# prject_arkom_robot_running_folower.net
KiCad netlist of a schematic drawn in EAGLE
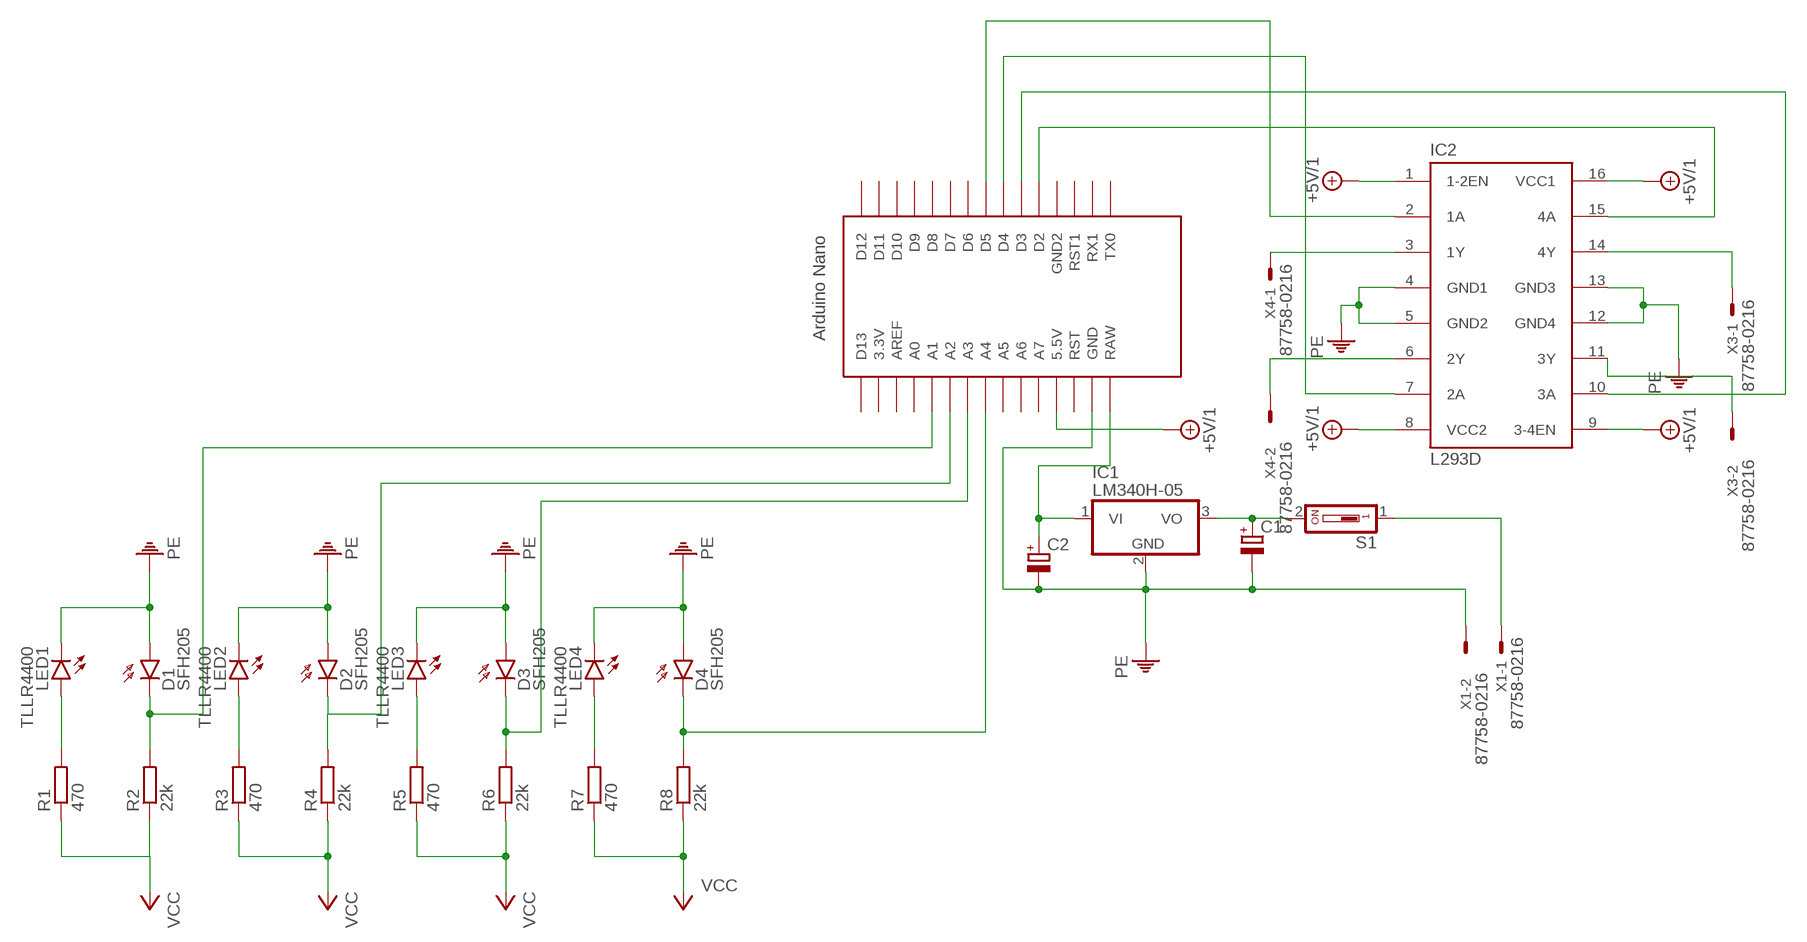
[diagram p0: schematic, sheet 1]

(export (version "E")
  (design (tool "Eeschema 10.0.6"))
  (components
    (comp (ref "C1")
      (value "CPOL-EUE2.5-7")
      (footprint "eagle-import:E2,5-7")
      (libsource (lib "eagle-import") (part "CPOL-EUE2.5-7"))
    )
    (comp (ref "C2")
      (value "CPOL-EUE2.5-7")
      (footprint "eagle-import:E2,5-7")
      (libsource (lib "eagle-import") (part "CPOL-EUE2.5-7"))
    )
    (comp (ref "D1")
      (value "SFH205")
      (footprint "eagle-import:SFH205")
      (libsource (lib "eagle-import") (part "SFH205"))
    )
    (comp (ref "D2")
      (value "SFH205")
      (footprint "eagle-import:SFH205")
      (libsource (lib "eagle-import") (part "SFH205"))
    )
    (comp (ref "D3")
      (value "SFH205")
      (footprint "eagle-import:SFH205")
      (libsource (lib "eagle-import") (part "SFH205"))
    )
    (comp (ref "D4")
      (value "SFH205")
      (footprint "eagle-import:SFH205")
      (libsource (lib "eagle-import") (part "SFH205"))
    )
    (comp (ref "IC1")
      (value "LM340H-05")
      (footprint "eagle-import:TO220H")
      (libsource (lib "eagle-import") (part "LM340?-H05"))
    )
    (comp (ref "IC2")
      (value "L293D")
      (footprint "eagle-import:DIL16")
      (libsource (lib "eagle-import") (part "L293D"))
    )
    (comp (ref "LED1")
      (value "TLLR4400")
      (footprint "eagle-import:LED3MM")
      (fields (field (name "MF") "VISHAY SEMICONDUCTOR"))
      (libsource (lib "eagle-import") (part "TLLR4400"))
    )
    (comp (ref "LED2")
      (value "TLLR4400")
      (footprint "eagle-import:LED3MM")
      (fields (field (name "MF") "VISHAY SEMICONDUCTOR"))
      (libsource (lib "eagle-import") (part "TLLR4400"))
    )
    (comp (ref "LED3")
      (value "TLLR4400")
      (footprint "eagle-import:LED3MM")
      (fields (field (name "MF") "VISHAY SEMICONDUCTOR"))
      (libsource (lib "eagle-import") (part "TLLR4400"))
    )
    (comp (ref "LED4")
      (value "TLLR4400")
      (footprint "eagle-import:LED3MM")
      (fields (field (name "MF") "VISHAY SEMICONDUCTOR"))
      (libsource (lib "eagle-import") (part "TLLR4400"))
    )
    (comp (ref "R1")
      (value "470")
      (footprint "eagle-import:0204_7")
      (libsource (lib "eagle-import") (part "R-EU_0204/7"))
    )
    (comp (ref "R2")
      (value "22k")
      (footprint "eagle-import:0204_7")
      (libsource (lib "eagle-import") (part "R-EU_0204/7"))
    )
    (comp (ref "R3")
      (value "470")
      (footprint "eagle-import:0204_7")
      (libsource (lib "eagle-import") (part "R-EU_0204/7"))
    )
    (comp (ref "R4")
      (value "22k")
      (footprint "eagle-import:0204_7")
      (libsource (lib "eagle-import") (part "R-EU_0204/7"))
    )
    (comp (ref "R5")
      (value "470")
      (footprint "eagle-import:0204_7")
      (libsource (lib "eagle-import") (part "R-EU_0204/7"))
    )
    (comp (ref "R6")
      (value "22k")
      (footprint "eagle-import:0204_7")
      (libsource (lib "eagle-import") (part "R-EU_0204/7"))
    )
    (comp (ref "R7")
      (value "470")
      (footprint "eagle-import:0204_7")
      (libsource (lib "eagle-import") (part "R-EU_0204/7"))
    )
    (comp (ref "R8")
      (value "22k")
      (footprint "eagle-import:0204_7")
      (libsource (lib "eagle-import") (part "R-EU_0204/7"))
    )
    (comp (ref "S1")
      (value "SD4-01")
      (footprint "eagle-import:SD4-01")
      (libsource (lib "eagle-import") (part "SD4-01"))
    )
    (comp (ref "U$1")
      (value "NANO")
      (footprint "eagle-import:NANO")
      (libsource (lib "eagle-import") (part "NANO"))
    )
    (comp (ref "X1")
      (value "87758-0216")
      (footprint "eagle-import:87758-0216")
      (fields (field (name "MF") "MOLEX"))
      (libsource (lib "eagle-import") (part "87758-0216"))
    )
    (comp (ref "X3")
      (value "87758-0216")
      (footprint "eagle-import:87758-0216")
      (fields (field (name "MF") "MOLEX"))
      (libsource (lib "eagle-import") (part "87758-0216"))
    )
    (comp (ref "X4")
      (value "87758-0216")
      (footprint "eagle-import:87758-0216")
      (fields (field (name "MF") "MOLEX"))
      (libsource (lib "eagle-import") (part "87758-0216"))
    )
  )
  (nets
    (net (code "1") (name "+5V{slash}1") (class "Default")
      (node (ref "IC2") (pin "1") (pinfunction "1-2EN_1") (pintype "input"))
      (node (ref "IC2") (pin "16") (pinfunction "VCC1_16") (pintype "power_in"))
      (node (ref "IC2") (pin "8") (pinfunction "VCC2_8") (pintype "power_in"))
      (node (ref "IC2") (pin "9") (pinfunction "3-4EN_9") (pintype "input"))
      (node (ref "U$1") (pin "5V") (pinfunction "5.5V_5V") (pintype "bidirectional"))
    )
    (net (code "2") (name "Net-(D1-C)") (class "Default")
      (node (ref "D1") (pin "K") (pinfunction "C_K") (pintype "passive"))
      (node (ref "R2") (pin "2") (pinfunction "2_2") (pintype "passive"))
      (node (ref "U$1") (pin "A1") (pinfunction "A1_A1") (pintype "bidirectional"))
    )
    (net (code "3") (name "Net-(D2-C)") (class "Default")
      (node (ref "D2") (pin "K") (pinfunction "C_K") (pintype "passive"))
      (node (ref "R4") (pin "2") (pinfunction "2_2") (pintype "passive"))
      (node (ref "U$1") (pin "A2") (pinfunction "A2_A2") (pintype "bidirectional"))
    )
    (net (code "4") (name "Net-(D3-C)") (class "Default")
      (node (ref "D3") (pin "K") (pinfunction "C_K") (pintype "passive"))
      (node (ref "R6") (pin "2") (pinfunction "2_2") (pintype "passive"))
      (node (ref "U$1") (pin "A3") (pinfunction "A3_A3") (pintype "bidirectional"))
    )
    (net (code "5") (name "Net-(D4-C)") (class "Default")
      (node (ref "D4") (pin "K") (pinfunction "C_K") (pintype "passive"))
      (node (ref "R8") (pin "2") (pinfunction "2_2") (pintype "passive"))
      (node (ref "U$1") (pin "A4") (pinfunction "A4_A4") (pintype "bidirectional"))
    )
    (net (code "6") (name "Net-(IC1-VI)") (class "Default")
      (node (ref "C2") (pin "+") (pinfunction "+_+") (pintype "passive"))
      (node (ref "IC1") (pin "1") (pinfunction "VI_1") (pintype "input"))
      (node (ref "U$1") (pin "RAW") (pinfunction "RAW_RAW") (pintype "bidirectional"))
    )
    (net (code "7") (name "Net-(IC1-VO)") (class "Default")
      (node (ref "C1") (pin "+") (pinfunction "+_+") (pintype "passive"))
      (node (ref "IC1") (pin "3") (pinfunction "VO_3") (pintype "passive"))
      (node (ref "S1") (pin "2") (pinfunction "2_2") (pintype "passive"))
    )
    (net (code "8") (name "Net-(IC2-1A)") (class "Default")
      (node (ref "IC2") (pin "2") (pinfunction "1A_2") (pintype "input"))
      (node (ref "U$1") (pin "D5") (pinfunction "D5_D5") (pintype "bidirectional"))
    )
    (net (code "9") (name "Net-(IC2-1Y)") (class "Default")
      (node (ref "IC2") (pin "3") (pinfunction "1Y_3") (pintype "output"))
      (node (ref "X4") (pin "1") (pinfunction "S_1") (pintype "passive"))
    )
    (net (code "10") (name "Net-(IC2-2A)") (class "Default")
      (node (ref "IC2") (pin "7") (pinfunction "2A_7") (pintype "input"))
      (node (ref "U$1") (pin "D4") (pinfunction "D4_D4") (pintype "bidirectional"))
    )
    (net (code "11") (name "Net-(IC2-2Y)") (class "Default")
      (node (ref "IC2") (pin "6") (pinfunction "2Y_6") (pintype "output"))
      (node (ref "X4") (pin "2") (pinfunction "S_2") (pintype "passive"))
    )
    (net (code "12") (name "Net-(IC2-3A)") (class "Default")
      (node (ref "IC2") (pin "10") (pinfunction "3A_10") (pintype "input"))
      (node (ref "U$1") (pin "D3") (pinfunction "D3_D3") (pintype "bidirectional"))
    )
    (net (code "13") (name "Net-(IC2-3Y)") (class "Default")
      (node (ref "IC2") (pin "11") (pinfunction "3Y_11") (pintype "output"))
      (node (ref "X3") (pin "2") (pinfunction "S_2") (pintype "passive"))
    )
    (net (code "14") (name "Net-(IC2-4A)") (class "Default")
      (node (ref "IC2") (pin "15") (pinfunction "4A_15") (pintype "input"))
      (node (ref "U$1") (pin "D2") (pinfunction "D2_D2") (pintype "bidirectional"))
    )
    (net (code "15") (name "Net-(IC2-4Y)") (class "Default")
      (node (ref "IC2") (pin "14") (pinfunction "4Y_14") (pintype "output"))
      (node (ref "X3") (pin "1") (pinfunction "S_1") (pintype "passive"))
    )
    (net (code "16") (name "Net-(LED1-PadA)") (class "Default")
      (node (ref "LED1") (pin "A") (pinfunction "A_A") (pintype "passive"))
      (node (ref "R1") (pin "2") (pinfunction "2_2") (pintype "passive"))
    )
    (net (code "17") (name "Net-(LED2-PadA)") (class "Default")
      (node (ref "LED2") (pin "A") (pinfunction "A_A") (pintype "passive"))
      (node (ref "R3") (pin "2") (pinfunction "2_2") (pintype "passive"))
    )
    (net (code "18") (name "Net-(LED3-PadA)") (class "Default")
      (node (ref "LED3") (pin "A") (pinfunction "A_A") (pintype "passive"))
      (node (ref "R5") (pin "2") (pinfunction "2_2") (pintype "passive"))
    )
    (net (code "19") (name "Net-(LED4-PadA)") (class "Default")
      (node (ref "LED4") (pin "A") (pinfunction "A_A") (pintype "passive"))
      (node (ref "R7") (pin "2") (pinfunction "2_2") (pintype "passive"))
    )
    (net (code "20") (name "Net-(X1A-S)") (class "Default")
      (node (ref "S1") (pin "1") (pinfunction "1_1") (pintype "passive"))
      (node (ref "X1") (pin "1") (pinfunction "S_1") (pintype "passive"))
    )
    (net (code "21") (name "PE") (class "Default")
      (node (ref "C1") (pin "-") (pinfunction "-_-") (pintype "passive"))
      (node (ref "C2") (pin "-") (pinfunction "-_-") (pintype "passive"))
      (node (ref "D1") (pin "A") (pinfunction "A_A") (pintype "passive"))
      (node (ref "D2") (pin "A") (pinfunction "A_A") (pintype "passive"))
      (node (ref "D3") (pin "A") (pinfunction "A_A") (pintype "passive"))
      (node (ref "D4") (pin "A") (pinfunction "A_A") (pintype "passive"))
      (node (ref "IC1") (pin "2") (pinfunction "GND_2") (pintype "passive"))
      (node (ref "IC2") (pin "12") (pinfunction "GND4_12") (pintype "power_in"))
      (node (ref "IC2") (pin "13") (pinfunction "GND3_13") (pintype "power_in"))
      (node (ref "IC2") (pin "4") (pinfunction "GND1_4") (pintype "power_in"))
      (node (ref "IC2") (pin "5") (pinfunction "GND2_5") (pintype "power_in"))
      (node (ref "LED1") (pin "K") (pinfunction "C_K") (pintype "passive"))
      (node (ref "LED2") (pin "K") (pinfunction "C_K") (pintype "passive"))
      (node (ref "LED3") (pin "K") (pinfunction "C_K") (pintype "passive"))
      (node (ref "LED4") (pin "K") (pinfunction "C_K") (pintype "passive"))
      (node (ref "U$1") (pin "GND") (pinfunction "GND_GND") (pintype "bidirectional"))
      (node (ref "X1") (pin "2") (pinfunction "S_2") (pintype "passive"))
    )
    (net (code "22") (name "VCC") (class "Default")
      (node (ref "R1") (pin "1") (pinfunction "1_1") (pintype "passive"))
      (node (ref "R2") (pin "1") (pinfunction "1_1") (pintype "passive"))
      (node (ref "R3") (pin "1") (pinfunction "1_1") (pintype "passive"))
      (node (ref "R4") (pin "1") (pinfunction "1_1") (pintype "passive"))
      (node (ref "R5") (pin "1") (pinfunction "1_1") (pintype "passive"))
      (node (ref "R6") (pin "1") (pinfunction "1_1") (pintype "passive"))
      (node (ref "R7") (pin "1") (pinfunction "1_1") (pintype "passive"))
      (node (ref "R8") (pin "1") (pinfunction "1_1") (pintype "passive"))
    )
    (net (code "23") (name "unconnected-(U$1-GND2-PadGND1)") (class "Default")
      (node (ref "U$1") (pin "GND1") (pinfunction "GND2_GND1") (pintype "bidirectional"))
    )
    (net (code "24") (name "unconnected-(U$1-Pad3.3V)") (class "Default")
      (node (ref "U$1") (pin "3.3V") (pinfunction "3.3V_3.3V") (pintype "bidirectional"))
    )
    (net (code "25") (name "unconnected-(U$1-PadA0)") (class "Default")
      (node (ref "U$1") (pin "A0") (pinfunction "A0_A0") (pintype "bidirectional"))
    )
    (net (code "26") (name "unconnected-(U$1-PadA5)") (class "Default")
      (node (ref "U$1") (pin "A5") (pinfunction "A5_A5") (pintype "bidirectional"))
    )
    (net (code "27") (name "unconnected-(U$1-PadA6)") (class "Default")
      (node (ref "U$1") (pin "A6") (pinfunction "A6_A6") (pintype "bidirectional"))
    )
    (net (code "28") (name "unconnected-(U$1-PadA7)") (class "Default")
      (node (ref "U$1") (pin "A7") (pinfunction "A7_A7") (pintype "bidirectional"))
    )
    (net (code "29") (name "unconnected-(U$1-PadAREF)") (class "Default")
      (node (ref "U$1") (pin "AREF") (pinfunction "AREF_AREF") (pintype "bidirectional"))
    )
    (net (code "30") (name "unconnected-(U$1-PadD6)") (class "Default")
      (node (ref "U$1") (pin "D6") (pinfunction "D6_D6") (pintype "bidirectional"))
    )
    (net (code "31") (name "unconnected-(U$1-PadD7)") (class "Default")
      (node (ref "U$1") (pin "D7") (pinfunction "D7_D7") (pintype "bidirectional"))
    )
    (net (code "32") (name "unconnected-(U$1-PadD8)") (class "Default")
      (node (ref "U$1") (pin "D8") (pinfunction "D8_D8") (pintype "bidirectional"))
    )
    (net (code "33") (name "unconnected-(U$1-PadD9)") (class "Default")
      (node (ref "U$1") (pin "D9") (pinfunction "D9_D9") (pintype "bidirectional"))
    )
    (net (code "34") (name "unconnected-(U$1-PadD10)") (class "Default")
      (node (ref "U$1") (pin "D10") (pinfunction "D10_D10") (pintype "bidirectional"))
    )
    (net (code "35") (name "unconnected-(U$1-PadD11)") (class "Default")
      (node (ref "U$1") (pin "D11") (pinfunction "D11_D11") (pintype "bidirectional"))
    )
    (net (code "36") (name "unconnected-(U$1-PadD12)") (class "Default")
      (node (ref "U$1") (pin "D12") (pinfunction "D12_D12") (pintype "bidirectional"))
    )
    (net (code "37") (name "unconnected-(U$1-PadD13)") (class "Default")
      (node (ref "U$1") (pin "D13") (pinfunction "D13_D13") (pintype "bidirectional"))
    )
    (net (code "38") (name "unconnected-(U$1-PadICSP1)") (class "Default")
      (node (ref "U$1") (pin "ICSP1") (pinfunction "ICSP1_ICSP1") (pintype "bidirectional"))
    )
    (net (code "39") (name "unconnected-(U$1-PadICSP2)") (class "Default")
      (node (ref "U$1") (pin "ICSP2") (pinfunction "ICSP2_ICSP2") (pintype "bidirectional"))
    )
    (net (code "40") (name "unconnected-(U$1-PadICSP3)") (class "Default")
      (node (ref "U$1") (pin "ICSP3") (pinfunction "ICSP3_ICSP3") (pintype "bidirectional"))
    )
    (net (code "41") (name "unconnected-(U$1-PadICSP4)") (class "Default")
      (node (ref "U$1") (pin "ICSP4") (pinfunction "ICSP4_ICSP4") (pintype "bidirectional"))
    )
    (net (code "42") (name "unconnected-(U$1-PadICSP5)") (class "Default")
      (node (ref "U$1") (pin "ICSP5") (pinfunction "ICSP5_ICSP5") (pintype "bidirectional"))
    )
    (net (code "43") (name "unconnected-(U$1-PadICSP6)") (class "Default")
      (node (ref "U$1") (pin "ICSP6") (pinfunction "ICSP6_ICSP6") (pintype "bidirectional"))
    )
    (net (code "44") (name "unconnected-(U$1-PadRST)") (class "Default")
      (node (ref "U$1") (pin "RST") (pinfunction "RST_RST") (pintype "bidirectional"))
    )
    (net (code "45") (name "unconnected-(U$1-PadRST1)") (class "Default")
      (node (ref "U$1") (pin "RST1") (pinfunction "RST1_RST1") (pintype "bidirectional"))
    )
    (net (code "46") (name "unconnected-(U$1-PadRX1)") (class "Default")
      (node (ref "U$1") (pin "RX1") (pinfunction "RX1_RX1") (pintype "bidirectional"))
    )
    (net (code "47") (name "unconnected-(U$1-PadTX0)") (class "Default")
      (node (ref "U$1") (pin "TX0") (pinfunction "TX0_TX0") (pintype "bidirectional"))
    )
  )
)
